# ledstringpowerRev1.net
KiCad netlist of a schematic drawn in EAGLE
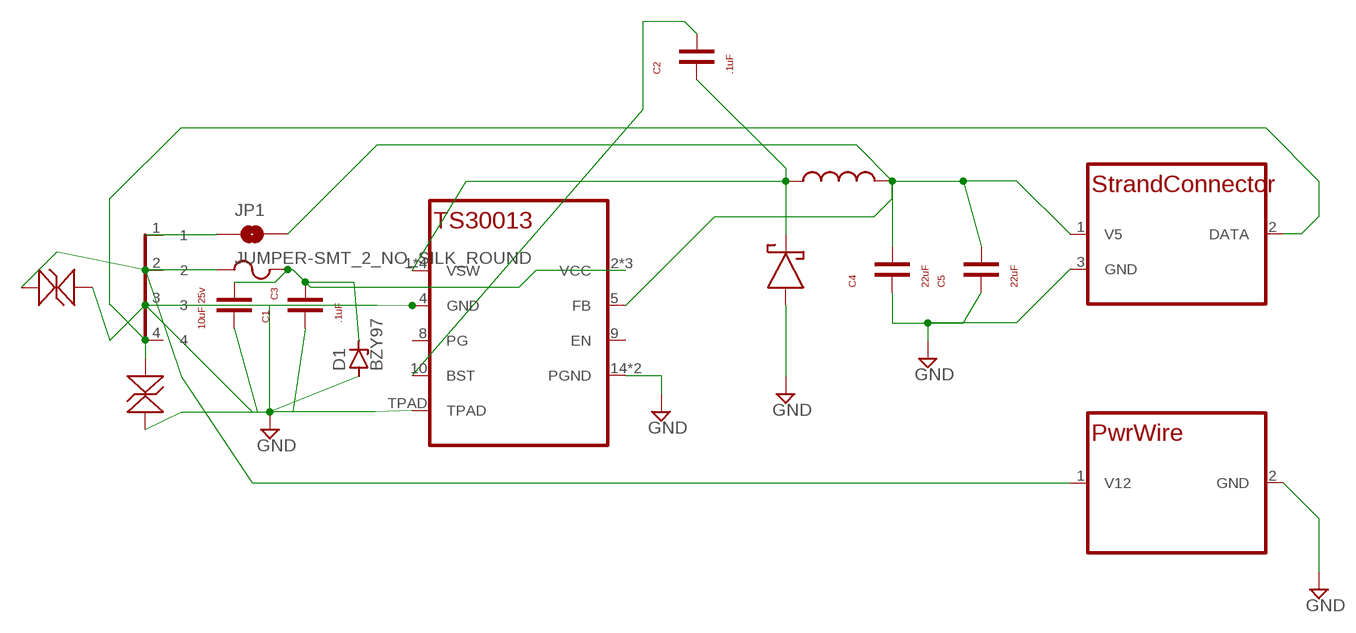
[diagram p0: schematic, sheet 1]

(export (version "E")
  (design (tool "Eeschema 10.0.6"))
  (components
    (comp (ref "C1")
      (value ".1uF")
      (footprint "eagle-import:C0603")
      (libsource (lib "eagle-import") (part "CAPACITOR_NONPOLARC0603"))
    )
    (comp (ref "C2")
      (value ".1uF")
      (footprint "eagle-import:C0603")
      (libsource (lib "eagle-import") (part "CAPACITOR_NONPOLARC0603"))
    )
    (comp (ref "C3")
      (value "10uF 25v")
      (footprint "eagle-import:C1206")
      (libsource (lib "eagle-import") (part "CL31A106MAHNNNEC1206"))
    )
    (comp (ref "C4")
      (value "22uF")
      (footprint "eagle-import:C0603")
      (libsource (lib "eagle-import") (part "GRM188R61A226ME15DC0603"))
    )
    (comp (ref "C5")
      (value "22uF")
      (footprint "eagle-import:C0603")
      (libsource (lib "eagle-import") (part "GRM188R61A226ME15DC0603"))
    )
    (comp (ref "D1")
      (value "BZY97")
      (footprint "eagle-import:F126Z12")
      (libsource (lib "eagle-import") (part "BZY97"))
    )
    (comp (ref "D2")
      (value "LS54LS54")
      (footprint "eagle-import:LS54")
      (libsource (lib "eagle-import") (part "LS54LS54"))
    )
    (comp (ref "F1")
      (value "3A")
      (footprint "eagle-import:R0603")
      (libsource (lib "eagle-import") (part "FUSER0603"))
    )
    (comp (ref "IC1")
      (value "TS30013QFN16")
      (footprint "eagle-import:QFN16")
      (libsource (lib "eagle-import") (part "TS30013QFN16"))
    )
    (comp (ref "JP1")
      (value "JUMPER-SMT_2_NO_SILK_ROUND")
      (footprint "eagle-import:SMT-JUMPER_2_NO_SILK_ROUND")
      (libsource (lib "eagle-import") (part "JUMPER-SMT_2_NO_SILK_ROUND"))
    )
    (comp (ref "L1")
      (value "SRN5040TA-4R7MSRN5040TA")
      (footprint "eagle-import:SRN5040TA")
      (libsource (lib "eagle-import") (part "SRN5040TA-4R7MSRN5040TA"))
    )
    (comp (ref "TVS1")
      (value "DESD5V0U1BL-7BDFN1006-2")
      (footprint "eagle-import:DFN1006-2")
      (libsource (lib "eagle-import") (part "DESD5V0U1BL-7BDFN1006-2"))
    )
    (comp (ref "TVS2")
      (value "DESD5V0U1BL-7BDFN1006-2")
      (footprint "eagle-import:DFN1006-2")
      (libsource (lib "eagle-import") (part "DESD5V0U1BL-7BDFN1006-2"))
    )
    (comp (ref "U$3")
      (value "TE-1969806-1TE-1969806-1")
      (footprint "eagle-import:TE-1969806-1")
      (libsource (lib "eagle-import") (part "TE-1969806-1TE-1969806-1"))
    )
    (comp (ref "U$5")
      (value "LEDSTRANDDLEDWIREP")
      (footprint "eagle-import:LEDWIREP")
      (libsource (lib "eagle-import") (part "LEDSTRANDDLEDWIREP"))
    )
    (comp (ref "U$8")
      (value "PWRWIREDPWRWIREP")
      (footprint "eagle-import:PWRWIREP")
      (libsource (lib "eagle-import") (part "PWRWIREDPWRWIREP"))
    )
  )
  (nets
    (net (code "1") (name "GND") (class "Default")
      (node (ref "C1") (pin "1") (pinfunction "1_1") (pintype "bidirectional"))
      (node (ref "C3") (pin "2") (pinfunction "2_2") (pintype "bidirectional"))
      (node (ref "C4") (pin "1") (pinfunction "1_1") (pintype "bidirectional"))
      (node (ref "C5") (pin "1") (pinfunction "1_1") (pintype "bidirectional"))
      (node (ref "D1") (pin "A") (pinfunction "A_A") (pintype "passive"))
      (node (ref "D2") (pin "1") (pinfunction "1_1") (pintype "bidirectional"))
      (node (ref "IC1") (pin "14") (pinfunction "PGND_14") (pintype "bidirectional"))
      (node (ref "IC1") (pin "15") (pinfunction "PGND_15") (pintype "bidirectional"))
      (node (ref "IC1") (pin "4") (pinfunction "GND_4") (pintype "bidirectional"))
      (node (ref "IC1") (pin "TPAD") (pinfunction "TPAD_TPAD") (pintype "bidirectional"))
      (node (ref "TVS1") (pin "1") (pinfunction "1_1") (pintype "bidirectional"))
      (node (ref "TVS2") (pin "1") (pinfunction "1_1") (pintype "bidirectional"))
      (node (ref "U$3") (pin "3") (pinfunction "3_3") (pintype "bidirectional"))
      (node (ref "U$5") (pin "3") (pinfunction "GND_3") (pintype "bidirectional"))
      (node (ref "U$8") (pin "2") (pinfunction "GND_2") (pintype "bidirectional"))
    )
    (net (code "2") (name "Net-(C1-Pad2)") (class "Default")
      (node (ref "C1") (pin "2") (pinfunction "2_2") (pintype "bidirectional"))
      (node (ref "C3") (pin "1") (pinfunction "1_1") (pintype "bidirectional"))
      (node (ref "D1") (pin "C") (pinfunction "C_C") (pintype "passive"))
      (node (ref "F1") (pin "2") (pinfunction "2_2") (pintype "bidirectional"))
      (node (ref "IC1") (pin "11") (pinfunction "VCC_11") (pintype "bidirectional"))
      (node (ref "IC1") (pin "2") (pinfunction "VCC_2") (pintype "bidirectional"))
      (node (ref "IC1") (pin "3") (pinfunction "VCC_3") (pintype "bidirectional"))
    )
    (net (code "3") (name "Net-(C2-Pad1)") (class "Default")
      (node (ref "C2") (pin "1") (pinfunction "1_1") (pintype "bidirectional"))
      (node (ref "D2") (pin "2") (pinfunction "2_2") (pintype "bidirectional"))
      (node (ref "IC1") (pin "1") (pinfunction "VSW_1") (pintype "bidirectional"))
      (node (ref "IC1") (pin "12") (pinfunction "VSW_12") (pintype "bidirectional"))
      (node (ref "IC1") (pin "13") (pinfunction "VSW_13") (pintype "bidirectional"))
      (node (ref "IC1") (pin "16") (pinfunction "VSW_16") (pintype "bidirectional"))
      (node (ref "L1") (pin "1") (pinfunction "1_1") (pintype "bidirectional"))
    )
    (net (code "4") (name "Net-(IC1-BST)") (class "Default")
      (node (ref "C2") (pin "2") (pinfunction "2_2") (pintype "bidirectional"))
      (node (ref "IC1") (pin "10") (pinfunction "BST_10") (pintype "bidirectional"))
    )
    (net (code "5") (name "Net-(IC1-FB)") (class "Default")
      (node (ref "C4") (pin "2") (pinfunction "2_2") (pintype "bidirectional"))
      (node (ref "C5") (pin "2") (pinfunction "2_2") (pintype "bidirectional"))
      (node (ref "IC1") (pin "5") (pinfunction "FB_5") (pintype "bidirectional"))
      (node (ref "JP1") (pin "2") (pinfunction "2_2") (pintype "passive"))
      (node (ref "L1") (pin "2") (pinfunction "2_2") (pintype "bidirectional"))
      (node (ref "U$5") (pin "1") (pinfunction "V5_1") (pintype "bidirectional"))
    )
    (net (code "6") (name "Net-(JP1-Pad1)") (class "Default")
      (node (ref "JP1") (pin "1") (pinfunction "1_1") (pintype "passive"))
      (node (ref "U$3") (pin "1") (pinfunction "1_1") (pintype "bidirectional"))
    )
    (net (code "7") (name "Net-(U$5-DATA)") (class "Default")
      (node (ref "TVS2") (pin "2") (pinfunction "2_2") (pintype "bidirectional"))
      (node (ref "U$3") (pin "4") (pinfunction "4_4") (pintype "bidirectional"))
      (node (ref "U$5") (pin "2") (pinfunction "DATA_2") (pintype "bidirectional"))
    )
    (net (code "8") (name "Net-(U$8-V12)") (class "Default")
      (node (ref "F1") (pin "1") (pinfunction "1_1") (pintype "bidirectional"))
      (node (ref "TVS1") (pin "2") (pinfunction "2_2") (pintype "bidirectional"))
      (node (ref "U$3") (pin "2") (pinfunction "2_2") (pintype "bidirectional"))
      (node (ref "U$8") (pin "1") (pinfunction "V12_1") (pintype "bidirectional"))
    )
    (net (code "9") (name "unconnected-(IC1-EN-Pad9)") (class "Default")
      (node (ref "IC1") (pin "9") (pinfunction "EN_9") (pintype "bidirectional"))
    )
    (net (code "10") (name "unconnected-(IC1-PG-Pad8)") (class "Default")
      (node (ref "IC1") (pin "8") (pinfunction "PG_8") (pintype "bidirectional"))
    )
  )
)
